# FPGA.net
KiCad netlist of a schematic drawn in Altium Designer
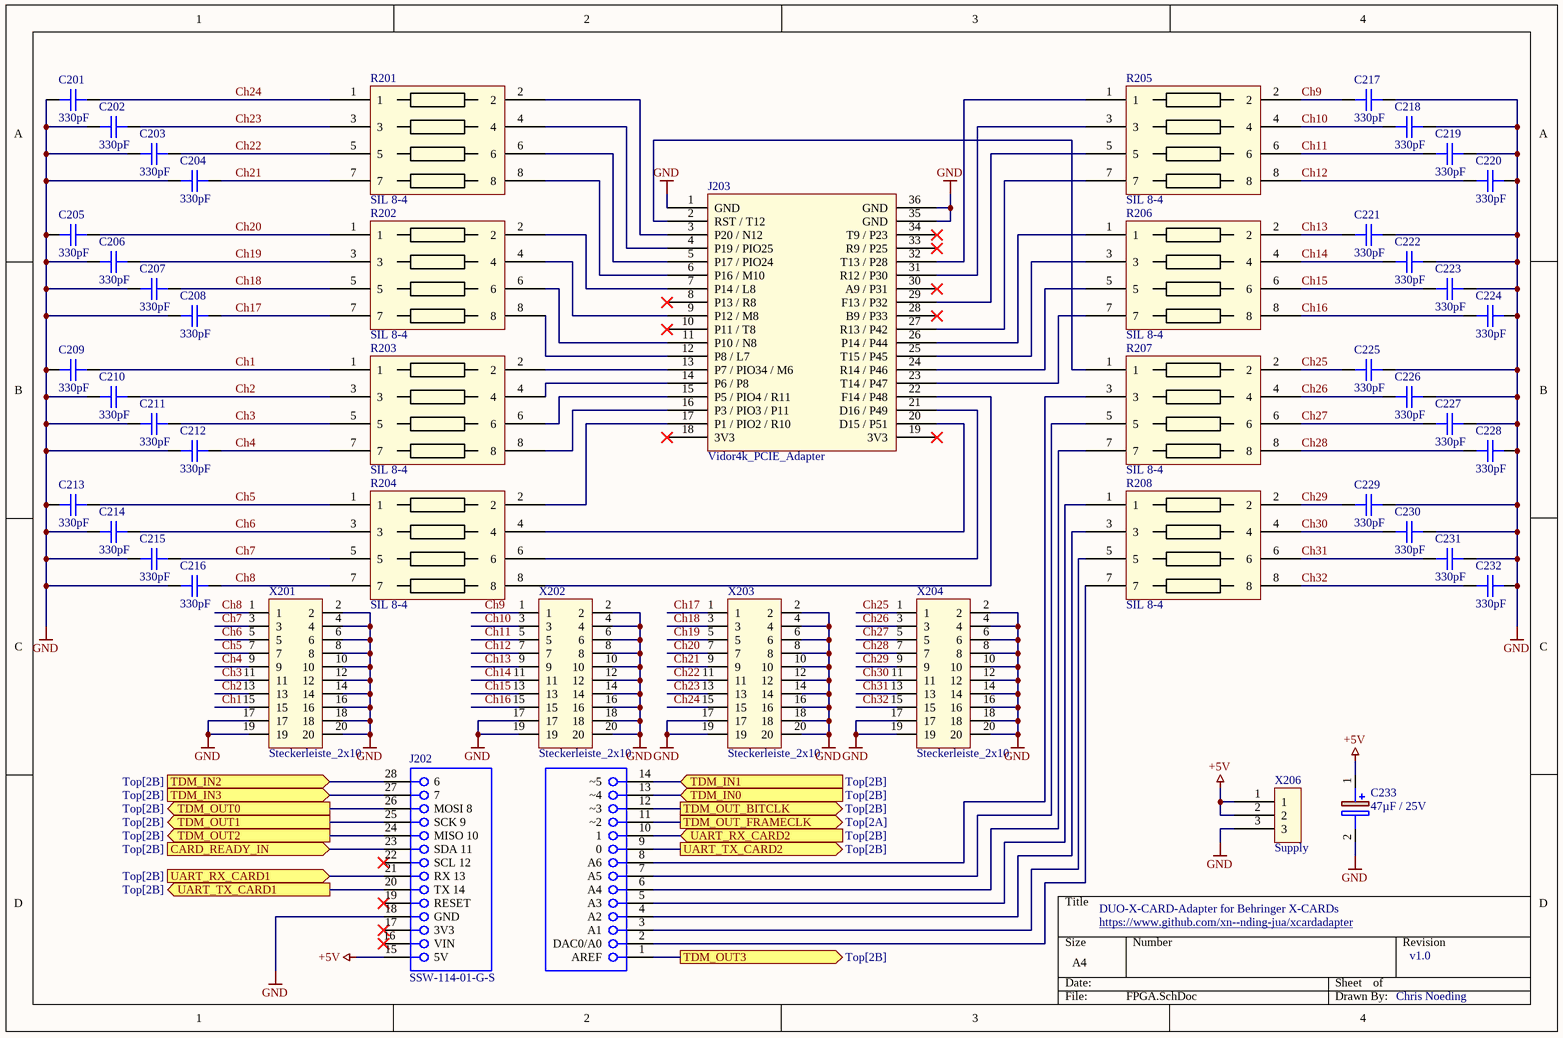
[diagram p0: FPGA.SchDoc]

(export (version "E")
  (design (tool "Eeschema 10.0.6"))
  (components
    (comp (ref "C201")
      (value "330pF")
      (footprint "1206")
      (description "1206_C")
      (libsource (lib "FPGA_Board_Library") (part "1206_C_1nF/63V"))
    )
    (comp (ref "C202")
      (value "330pF")
      (footprint "1206")
      (description "1206_C")
      (libsource (lib "FPGA_Board_Library") (part "1206_C_1nF/63V"))
    )
    (comp (ref "C203")
      (value "330pF")
      (footprint "1206")
      (description "1206_C")
      (libsource (lib "FPGA_Board_Library") (part "1206_C_1nF/63V"))
    )
    (comp (ref "C204")
      (value "330pF")
      (footprint "1206")
      (description "1206_C")
      (libsource (lib "FPGA_Board_Library") (part "1206_C_1nF/63V"))
    )
    (comp (ref "C205")
      (value "330pF")
      (footprint "1206")
      (description "1206_C")
      (libsource (lib "FPGA_Board_Library") (part "1206_C_1nF/63V"))
    )
    (comp (ref "C206")
      (value "330pF")
      (footprint "1206")
      (description "1206_C")
      (libsource (lib "FPGA_Board_Library") (part "1206_C_1nF/63V"))
    )
    (comp (ref "C207")
      (value "330pF")
      (footprint "1206")
      (description "1206_C")
      (libsource (lib "FPGA_Board_Library") (part "1206_C_1nF/63V"))
    )
    (comp (ref "C208")
      (value "330pF")
      (footprint "1206")
      (description "1206_C")
      (libsource (lib "FPGA_Board_Library") (part "1206_C_1nF/63V"))
    )
    (comp (ref "C209")
      (value "330pF")
      (footprint "1206")
      (description "1206_C")
      (libsource (lib "FPGA_Board_Library") (part "1206_C_1nF/63V"))
    )
    (comp (ref "C210")
      (value "330pF")
      (footprint "1206")
      (description "1206_C")
      (libsource (lib "FPGA_Board_Library") (part "1206_C_1nF/63V"))
    )
    (comp (ref "C211")
      (value "330pF")
      (footprint "1206")
      (description "1206_C")
      (libsource (lib "FPGA_Board_Library") (part "1206_C_1nF/63V"))
    )
    (comp (ref "C212")
      (value "330pF")
      (footprint "1206")
      (description "1206_C")
      (libsource (lib "FPGA_Board_Library") (part "1206_C_1nF/63V"))
    )
    (comp (ref "C213")
      (value "330pF")
      (footprint "1206")
      (description "1206_C")
      (libsource (lib "FPGA_Board_Library") (part "1206_C_1nF/63V"))
    )
    (comp (ref "C214")
      (value "330pF")
      (footprint "1206")
      (description "1206_C")
      (libsource (lib "FPGA_Board_Library") (part "1206_C_1nF/63V"))
    )
    (comp (ref "C215")
      (value "330pF")
      (footprint "1206")
      (description "1206_C")
      (libsource (lib "FPGA_Board_Library") (part "1206_C_1nF/63V"))
    )
    (comp (ref "C216")
      (value "330pF")
      (footprint "1206")
      (description "1206_C")
      (libsource (lib "FPGA_Board_Library") (part "1206_C_1nF/63V"))
    )
    (comp (ref "C217")
      (value "330pF")
      (footprint "1206")
      (description "1206_C")
      (libsource (lib "FPGA_Board_Library") (part "1206_C_1nF/63V"))
    )
    (comp (ref "C218")
      (value "330pF")
      (footprint "1206")
      (description "1206_C")
      (libsource (lib "FPGA_Board_Library") (part "1206_C_1nF/63V"))
    )
    (comp (ref "C219")
      (value "330pF")
      (footprint "1206")
      (description "1206_C")
      (libsource (lib "FPGA_Board_Library") (part "1206_C_1nF/63V"))
    )
    (comp (ref "C220")
      (value "330pF")
      (footprint "1206")
      (description "1206_C")
      (libsource (lib "FPGA_Board_Library") (part "1206_C_1nF/63V"))
    )
    (comp (ref "C221")
      (value "330pF")
      (footprint "1206")
      (description "1206_C")
      (libsource (lib "FPGA_Board_Library") (part "1206_C_1nF/63V"))
    )
    (comp (ref "C222")
      (value "330pF")
      (footprint "1206")
      (description "1206_C")
      (libsource (lib "FPGA_Board_Library") (part "1206_C_1nF/63V"))
    )
    (comp (ref "C223")
      (value "330pF")
      (footprint "1206")
      (description "1206_C")
      (libsource (lib "FPGA_Board_Library") (part "1206_C_1nF/63V"))
    )
    (comp (ref "C224")
      (value "330pF")
      (footprint "1206")
      (description "1206_C")
      (libsource (lib "FPGA_Board_Library") (part "1206_C_1nF/63V"))
    )
    (comp (ref "C225")
      (value "330pF")
      (footprint "1206")
      (description "1206_C")
      (libsource (lib "FPGA_Board_Library") (part "1206_C_1nF/63V"))
    )
    (comp (ref "C226")
      (value "330pF")
      (footprint "1206")
      (description "1206_C")
      (libsource (lib "FPGA_Board_Library") (part "1206_C_1nF/63V"))
    )
    (comp (ref "C227")
      (value "330pF")
      (footprint "1206")
      (description "1206_C")
      (libsource (lib "FPGA_Board_Library") (part "1206_C_1nF/63V"))
    )
    (comp (ref "C228")
      (value "330pF")
      (footprint "1206")
      (description "1206_C")
      (libsource (lib "FPGA_Board_Library") (part "1206_C_1nF/63V"))
    )
    (comp (ref "C229")
      (value "330pF")
      (footprint "1206")
      (description "1206_C")
      (libsource (lib "FPGA_Board_Library") (part "1206_C_1nF/63V"))
    )
    (comp (ref "C230")
      (value "330pF")
      (footprint "1206")
      (description "1206_C")
      (libsource (lib "FPGA_Board_Library") (part "1206_C_1nF/63V"))
    )
    (comp (ref "C231")
      (value "330pF")
      (footprint "1206")
      (description "1206_C")
      (libsource (lib "FPGA_Board_Library") (part "1206_C_1nF/63V"))
    )
    (comp (ref "C232")
      (value "330pF")
      (footprint "1206")
      (description "1206_C")
      (libsource (lib "FPGA_Board_Library") (part "1206_C_1nF/63V"))
    )
    (comp (ref "C233")
      (value "47µF / 25V")
      (footprint "SamacSys:CAPPRD200W50D550H1250")
      (description "Capacitor Polarised")
      (fields (field (name "MANUFACTURER_PART_NUMBER") "MAL214256479E3"))
      (libsource (lib "*") (part "MAL214256479E3"))
    )
    (comp (ref "J202")
      (value "SSW-114-01-G-S")
      (footprint "SMTC-SSW-114-01-X-S")
      (description "SQ Post Socket, Through-hole, Vertical, -55 to 125 degC, 2.54 mm Pitch, 14-Pin, Female, RoHS")
      (fields (field (name "MANUFACTURER") "Samtec"))
      (libsource (lib "SamacSys") (part "Arduino MKR Vidor 4000"))
    )
    (comp (ref "J203")
      (value "Vidor4k_PCIE_Adapter")
      (footprint "Vidor4K_PCIE_Adapter")
      (libsource (lib "SamacSys") (part "Vidor4k_PCIE_Adapter"))
    )
    (comp (ref "R201")
      (value "SIL 8-4")
      (footprint "SIL8")
      (libsource (lib "XCARD_Adapter") (part "SIL 8-4"))
    )
    (comp (ref "R202")
      (value "SIL 8-4")
      (footprint "SIL8")
      (libsource (lib "XCARD_Adapter") (part "SIL 8-4"))
    )
    (comp (ref "R203")
      (value "SIL 8-4")
      (footprint "SIL8")
      (libsource (lib "XCARD_Adapter") (part "SIL 8-4"))
    )
    (comp (ref "R204")
      (value "SIL 8-4")
      (footprint "SIL8")
      (libsource (lib "XCARD_Adapter") (part "SIL 8-4"))
    )
    (comp (ref "R205")
      (value "SIL 8-4")
      (footprint "SIL8")
      (libsource (lib "XCARD_Adapter") (part "SIL 8-4"))
    )
    (comp (ref "R206")
      (value "SIL 8-4")
      (footprint "SIL8")
      (libsource (lib "XCARD_Adapter") (part "SIL 8-4"))
    )
    (comp (ref "R207")
      (value "SIL 8-4")
      (footprint "SIL8")
      (libsource (lib "XCARD_Adapter") (part "SIL 8-4"))
    )
    (comp (ref "R208")
      (value "SIL 8-4")
      (footprint "SIL8")
      (libsource (lib "XCARD_Adapter") (part "SIL 8-4"))
    )
    (comp (ref "X201")
      (value "Steckerleiste_2x10")
      (footprint "steckerleiste_2x10")
      (libsource (lib "FPGA_Board_Library") (part "Steckerleiste_2x10"))
    )
    (comp (ref "X202")
      (value "Steckerleiste_2x10")
      (footprint "steckerleiste_2x10")
      (libsource (lib "FPGA_Board_Library") (part "Steckerleiste_2x10"))
    )
    (comp (ref "X203")
      (value "Steckerleiste_2x10")
      (footprint "steckerleiste_2x10")
      (libsource (lib "FPGA_Board_Library") (part "Steckerleiste_2x10"))
    )
    (comp (ref "X204")
      (value "Steckerleiste_2x10")
      (footprint "steckerleiste_2x10")
      (libsource (lib "FPGA_Board_Library") (part "Steckerleiste_2x10"))
    )
    (comp (ref "X206")
      (value "Supply")
      (footprint "1x3 Jumper")
      (libsource (lib "KDEE_HiResPG") (part "1x3 Jumper"))
    )
  )
  (nets
    (net (code "1") (name "+5V") (class "Default")
      (node (ref "C233") (pin "1") (pinfunction "+_1") (pintype "passive"))
      (node (ref "J202") (pin "15") (pinfunction "5V_15") (pintype "passive"))
      (node (ref "X206") (pin "1") (pinfunction "1_1") (pintype "passive"))
      (node (ref "X206") (pin "2") (pinfunction "2_2") (pintype "passive"))
    )
    (net (code "2") (name "/CARD_READY_IN") (class "Default")
      (node (ref "J202") (pin "23") (pinfunction "SDA_11_23") (pintype "passive"))
    )
    (net (code "3") (name "/Ch1") (class "Default")
      (node (ref "C209") (pin "1") (pinfunction "1_1") (pintype "passive"))
      (node (ref "R203") (pin "1") (pinfunction "1_1") (pintype "passive"))
      (node (ref "X201") (pin "15") (pinfunction "15_15") (pintype "passive"))
    )
    (net (code "4") (name "/Ch2") (class "Default")
      (node (ref "C210") (pin "1") (pinfunction "1_1") (pintype "passive"))
      (node (ref "R203") (pin "3") (pinfunction "3_3") (pintype "passive"))
      (node (ref "X201") (pin "13") (pinfunction "13_13") (pintype "passive"))
    )
    (net (code "5") (name "/Ch3") (class "Default")
      (node (ref "C211") (pin "1") (pinfunction "1_1") (pintype "passive"))
      (node (ref "R203") (pin "5") (pinfunction "5_5") (pintype "passive"))
      (node (ref "X201") (pin "11") (pinfunction "11_11") (pintype "passive"))
    )
    (net (code "6") (name "/Ch4") (class "Default")
      (node (ref "C212") (pin "1") (pinfunction "1_1") (pintype "passive"))
      (node (ref "R203") (pin "7") (pinfunction "7_7") (pintype "passive"))
      (node (ref "X201") (pin "9") (pinfunction "9_9") (pintype "passive"))
    )
    (net (code "7") (name "/Ch5") (class "Default")
      (node (ref "C213") (pin "1") (pinfunction "1_1") (pintype "passive"))
      (node (ref "R204") (pin "1") (pinfunction "1_1") (pintype "passive"))
      (node (ref "X201") (pin "7") (pinfunction "7_7") (pintype "passive"))
    )
    (net (code "8") (name "/Ch6") (class "Default")
      (node (ref "C214") (pin "1") (pinfunction "1_1") (pintype "passive"))
      (node (ref "R204") (pin "3") (pinfunction "3_3") (pintype "passive"))
      (node (ref "X201") (pin "5") (pinfunction "5_5") (pintype "passive"))
    )
    (net (code "9") (name "/Ch7") (class "Default")
      (node (ref "C215") (pin "1") (pinfunction "1_1") (pintype "passive"))
      (node (ref "R204") (pin "5") (pinfunction "5_5") (pintype "passive"))
      (node (ref "X201") (pin "3") (pinfunction "3_3") (pintype "passive"))
    )
    (net (code "10") (name "/Ch8") (class "Default")
      (node (ref "C216") (pin "1") (pinfunction "1_1") (pintype "passive"))
      (node (ref "R204") (pin "7") (pinfunction "7_7") (pintype "passive"))
      (node (ref "X201") (pin "1") (pinfunction "1_1") (pintype "passive"))
    )
    (net (code "11") (name "/Ch9") (class "Default")
      (node (ref "C217") (pin "2") (pinfunction "2_2") (pintype "passive"))
      (node (ref "R205") (pin "2") (pinfunction "2_2") (pintype "passive"))
      (node (ref "X202") (pin "1") (pinfunction "1_1") (pintype "passive"))
    )
    (net (code "12") (name "/Ch10") (class "Default")
      (node (ref "C218") (pin "2") (pinfunction "2_2") (pintype "passive"))
      (node (ref "R205") (pin "4") (pinfunction "4_4") (pintype "passive"))
      (node (ref "X202") (pin "3") (pinfunction "3_3") (pintype "passive"))
    )
    (net (code "13") (name "/Ch11") (class "Default")
      (node (ref "C219") (pin "2") (pinfunction "2_2") (pintype "passive"))
      (node (ref "R205") (pin "6") (pinfunction "6_6") (pintype "passive"))
      (node (ref "X202") (pin "5") (pinfunction "5_5") (pintype "passive"))
    )
    (net (code "14") (name "/Ch12") (class "Default")
      (node (ref "C220") (pin "2") (pinfunction "2_2") (pintype "passive"))
      (node (ref "R205") (pin "8") (pinfunction "8_8") (pintype "passive"))
      (node (ref "X202") (pin "7") (pinfunction "7_7") (pintype "passive"))
    )
    (net (code "15") (name "/Ch13") (class "Default")
      (node (ref "C221") (pin "2") (pinfunction "2_2") (pintype "passive"))
      (node (ref "R206") (pin "2") (pinfunction "2_2") (pintype "passive"))
      (node (ref "X202") (pin "9") (pinfunction "9_9") (pintype "passive"))
    )
    (net (code "16") (name "/Ch14") (class "Default")
      (node (ref "C222") (pin "2") (pinfunction "2_2") (pintype "passive"))
      (node (ref "R206") (pin "4") (pinfunction "4_4") (pintype "passive"))
      (node (ref "X202") (pin "11") (pinfunction "11_11") (pintype "passive"))
    )
    (net (code "17") (name "/Ch15") (class "Default")
      (node (ref "C223") (pin "2") (pinfunction "2_2") (pintype "passive"))
      (node (ref "R206") (pin "6") (pinfunction "6_6") (pintype "passive"))
      (node (ref "X202") (pin "13") (pinfunction "13_13") (pintype "passive"))
    )
    (net (code "18") (name "/Ch16") (class "Default")
      (node (ref "C224") (pin "2") (pinfunction "2_2") (pintype "passive"))
      (node (ref "R206") (pin "8") (pinfunction "8_8") (pintype "passive"))
      (node (ref "X202") (pin "15") (pinfunction "15_15") (pintype "passive"))
    )
    (net (code "19") (name "/Ch17") (class "Default")
      (node (ref "C208") (pin "1") (pinfunction "1_1") (pintype "passive"))
      (node (ref "R202") (pin "7") (pinfunction "7_7") (pintype "passive"))
      (node (ref "X203") (pin "1") (pinfunction "1_1") (pintype "passive"))
    )
    (net (code "20") (name "/Ch18") (class "Default")
      (node (ref "C207") (pin "1") (pinfunction "1_1") (pintype "passive"))
      (node (ref "R202") (pin "5") (pinfunction "5_5") (pintype "passive"))
      (node (ref "X203") (pin "3") (pinfunction "3_3") (pintype "passive"))
    )
    (net (code "21") (name "/Ch19") (class "Default")
      (node (ref "C206") (pin "1") (pinfunction "1_1") (pintype "passive"))
      (node (ref "R202") (pin "3") (pinfunction "3_3") (pintype "passive"))
      (node (ref "X203") (pin "5") (pinfunction "5_5") (pintype "passive"))
    )
    (net (code "22") (name "/Ch20") (class "Default")
      (node (ref "C205") (pin "1") (pinfunction "1_1") (pintype "passive"))
      (node (ref "R202") (pin "1") (pinfunction "1_1") (pintype "passive"))
      (node (ref "X203") (pin "7") (pinfunction "7_7") (pintype "passive"))
    )
    (net (code "23") (name "/Ch21") (class "Default")
      (node (ref "C204") (pin "1") (pinfunction "1_1") (pintype "passive"))
      (node (ref "R201") (pin "7") (pinfunction "7_7") (pintype "passive"))
      (node (ref "X203") (pin "9") (pinfunction "9_9") (pintype "passive"))
    )
    (net (code "24") (name "/Ch22") (class "Default")
      (node (ref "C203") (pin "1") (pinfunction "1_1") (pintype "passive"))
      (node (ref "R201") (pin "5") (pinfunction "5_5") (pintype "passive"))
      (node (ref "X203") (pin "11") (pinfunction "11_11") (pintype "passive"))
    )
    (net (code "25") (name "/Ch23") (class "Default")
      (node (ref "C202") (pin "1") (pinfunction "1_1") (pintype "passive"))
      (node (ref "R201") (pin "3") (pinfunction "3_3") (pintype "passive"))
      (node (ref "X203") (pin "13") (pinfunction "13_13") (pintype "passive"))
    )
    (net (code "26") (name "/Ch24") (class "Default")
      (node (ref "C201") (pin "1") (pinfunction "1_1") (pintype "passive"))
      (node (ref "R201") (pin "1") (pinfunction "1_1") (pintype "passive"))
      (node (ref "X203") (pin "15") (pinfunction "15_15") (pintype "passive"))
    )
    (net (code "27") (name "/Ch25") (class "Default")
      (node (ref "C225") (pin "2") (pinfunction "2_2") (pintype "passive"))
      (node (ref "R207") (pin "2") (pinfunction "2_2") (pintype "passive"))
      (node (ref "X204") (pin "1") (pinfunction "1_1") (pintype "passive"))
    )
    (net (code "28") (name "/Ch26") (class "Default")
      (node (ref "C226") (pin "2") (pinfunction "2_2") (pintype "passive"))
      (node (ref "R207") (pin "4") (pinfunction "4_4") (pintype "passive"))
      (node (ref "X204") (pin "3") (pinfunction "3_3") (pintype "passive"))
    )
    (net (code "29") (name "/Ch27") (class "Default")
      (node (ref "C227") (pin "2") (pinfunction "2_2") (pintype "passive"))
      (node (ref "R207") (pin "6") (pinfunction "6_6") (pintype "passive"))
      (node (ref "X204") (pin "5") (pinfunction "5_5") (pintype "passive"))
    )
    (net (code "30") (name "/Ch28") (class "Default")
      (node (ref "C228") (pin "2") (pinfunction "2_2") (pintype "passive"))
      (node (ref "R207") (pin "8") (pinfunction "8_8") (pintype "passive"))
      (node (ref "X204") (pin "7") (pinfunction "7_7") (pintype "passive"))
    )
    (net (code "31") (name "/Ch29") (class "Default")
      (node (ref "C229") (pin "2") (pinfunction "2_2") (pintype "passive"))
      (node (ref "R208") (pin "2") (pinfunction "2_2") (pintype "passive"))
      (node (ref "X204") (pin "9") (pinfunction "9_9") (pintype "passive"))
    )
    (net (code "32") (name "/Ch30") (class "Default")
      (node (ref "C230") (pin "2") (pinfunction "2_2") (pintype "passive"))
      (node (ref "R208") (pin "4") (pinfunction "4_4") (pintype "passive"))
      (node (ref "X204") (pin "11") (pinfunction "11_11") (pintype "passive"))
    )
    (net (code "33") (name "/Ch31") (class "Default")
      (node (ref "C231") (pin "2") (pinfunction "2_2") (pintype "passive"))
      (node (ref "R208") (pin "6") (pinfunction "6_6") (pintype "passive"))
      (node (ref "X204") (pin "13") (pinfunction "13_13") (pintype "passive"))
    )
    (net (code "34") (name "/Ch32") (class "Default")
      (node (ref "C232") (pin "2") (pinfunction "2_2") (pintype "passive"))
      (node (ref "R208") (pin "8") (pinfunction "8_8") (pintype "passive"))
      (node (ref "X204") (pin "15") (pinfunction "15_15") (pintype "passive"))
    )
    (net (code "35") (name "/TDM_IN0") (class "Default")
      (node (ref "J202") (pin "13") (pinfunction "~4_13") (pintype "passive"))
    )
    (net (code "36") (name "/TDM_IN1") (class "Default")
      (node (ref "J202") (pin "14") (pinfunction "~5_14") (pintype "passive"))
    )
    (net (code "37") (name "/TDM_IN2") (class "Default")
      (node (ref "J202") (pin "28") (pinfunction "6_28") (pintype "passive"))
    )
    (net (code "38") (name "/TDM_IN3") (class "Default")
      (node (ref "J202") (pin "27") (pinfunction "7_27") (pintype "passive"))
    )
    (net (code "39") (name "/TDM_OUT0") (class "Default")
      (node (ref "J202") (pin "26") (pinfunction "MOSI_8_26") (pintype "passive"))
    )
    (net (code "40") (name "/TDM_OUT1") (class "Default")
      (node (ref "J202") (pin "25") (pinfunction "SCK_9_25") (pintype "passive"))
    )
    (net (code "41") (name "/TDM_OUT2") (class "Default")
      (node (ref "J202") (pin "24") (pinfunction "MISO_10_24") (pintype "passive"))
    )
    (net (code "42") (name "/TDM_OUT3") (class "Default")
      (node (ref "J202") (pin "1") (pinfunction "AREF_1") (pintype "passive"))
    )
    (net (code "43") (name "/TDM_OUT_BITCLK") (class "Default")
      (node (ref "J202") (pin "12") (pinfunction "~3_12") (pintype "passive"))
    )
    (net (code "44") (name "/TDM_OUT_FRAMECLK") (class "Default")
      (node (ref "J202") (pin "11") (pinfunction "~2_11") (pintype "passive"))
    )
    (net (code "45") (name "/UART_RX_CARD1") (class "Default")
      (node (ref "J202") (pin "21") (pinfunction "RX_13_21") (pintype "passive"))
    )
    (net (code "46") (name "/UART_RX_CARD2") (class "Default")
      (node (ref "J202") (pin "10") (pinfunction "1_10") (pintype "passive"))
    )
    (net (code "47") (name "/UART_TX_CARD1") (class "Default")
      (node (ref "J202") (pin "20") (pinfunction "TX_14_20") (pintype "passive"))
    )
    (net (code "48") (name "/UART_TX_CARD2") (class "Default")
      (node (ref "J202") (pin "9") (pinfunction "0_9") (pintype "passive"))
    )
    (net (code "49") (name "GND") (class "Default")
      (node (ref "C201") (pin "2") (pinfunction "2_2") (pintype "passive"))
      (node (ref "C202") (pin "2") (pinfunction "2_2") (pintype "passive"))
      (node (ref "C203") (pin "2") (pinfunction "2_2") (pintype "passive"))
      (node (ref "C204") (pin "2") (pinfunction "2_2") (pintype "passive"))
      (node (ref "C205") (pin "2") (pinfunction "2_2") (pintype "passive"))
      (node (ref "C206") (pin "2") (pinfunction "2_2") (pintype "passive"))
      (node (ref "C207") (pin "2") (pinfunction "2_2") (pintype "passive"))
      (node (ref "C208") (pin "2") (pinfunction "2_2") (pintype "passive"))
      (node (ref "C209") (pin "2") (pinfunction "2_2") (pintype "passive"))
      (node (ref "C210") (pin "2") (pinfunction "2_2") (pintype "passive"))
      (node (ref "C211") (pin "2") (pinfunction "2_2") (pintype "passive"))
      (node (ref "C212") (pin "2") (pinfunction "2_2") (pintype "passive"))
      (node (ref "C213") (pin "2") (pinfunction "2_2") (pintype "passive"))
      (node (ref "C214") (pin "2") (pinfunction "2_2") (pintype "passive"))
      (node (ref "C215") (pin "2") (pinfunction "2_2") (pintype "passive"))
      (node (ref "C216") (pin "2") (pinfunction "2_2") (pintype "passive"))
      (node (ref "C217") (pin "1") (pinfunction "1_1") (pintype "passive"))
      (node (ref "C218") (pin "1") (pinfunction "1_1") (pintype "passive"))
      (node (ref "C219") (pin "1") (pinfunction "1_1") (pintype "passive"))
      (node (ref "C220") (pin "1") (pinfunction "1_1") (pintype "passive"))
      (node (ref "C221") (pin "1") (pinfunction "1_1") (pintype "passive"))
      (node (ref "C222") (pin "1") (pinfunction "1_1") (pintype "passive"))
      (node (ref "C223") (pin "1") (pinfunction "1_1") (pintype "passive"))
      (node (ref "C224") (pin "1") (pinfunction "1_1") (pintype "passive"))
      (node (ref "C225") (pin "1") (pinfunction "1_1") (pintype "passive"))
      (node (ref "C226") (pin "1") (pinfunction "1_1") (pintype "passive"))
      (node (ref "C227") (pin "1") (pinfunction "1_1") (pintype "passive"))
      (node (ref "C228") (pin "1") (pinfunction "1_1") (pintype "passive"))
      (node (ref "C229") (pin "1") (pinfunction "1_1") (pintype "passive"))
      (node (ref "C230") (pin "1") (pinfunction "1_1") (pintype "passive"))
      (node (ref "C231") (pin "1") (pinfunction "1_1") (pintype "passive"))
      (node (ref "C232") (pin "1") (pinfunction "1_1") (pintype "passive"))
      (node (ref "C233") (pin "2") (pinfunction "-_2") (pintype "passive"))
      (node (ref "J202") (pin "18") (pinfunction "GND_18") (pintype "passive"))
      (node (ref "J203") (pin "1") (pinfunction "GND_1") (pintype "passive"))
      (node (ref "J203") (pin "35") (pinfunction "GND_35") (pintype "passive"))
      (node (ref "J203") (pin "36") (pinfunction "GND_36") (pintype "passive"))
      (node (ref "X201") (pin "10") (pinfunction "10_10") (pintype "passive"))
      (node (ref "X201") (pin "12") (pinfunction "12_12") (pintype "passive"))
      (node (ref "X201") (pin "14") (pinfunction "14_14") (pintype "passive"))
      (node (ref "X201") (pin "16") (pinfunction "16_16") (pintype "passive"))
      (node (ref "X201") (pin "17") (pinfunction "17_17") (pintype "passive"))
      (node (ref "X201") (pin "18") (pinfunction "18_18") (pintype "passive"))
      (node (ref "X201") (pin "19") (pinfunction "19_19") (pintype "passive"))
      (node (ref "X201") (pin "2") (pinfunction "2_2") (pintype "passive"))
      (node (ref "X201") (pin "20") (pinfunction "20_20") (pintype "passive"))
      (node (ref "X201") (pin "4") (pinfunction "4_4") (pintype "passive"))
      (node (ref "X201") (pin "6") (pinfunction "6_6") (pintype "passive"))
      (node (ref "X201") (pin "8") (pinfunction "8_8") (pintype "passive"))
      (node (ref "X202") (pin "10") (pinfunction "10_10") (pintype "passive"))
      (node (ref "X202") (pin "12") (pinfunction "12_12") (pintype "passive"))
      (node (ref "X202") (pin "14") (pinfunction "14_14") (pintype "passive"))
      (node (ref "X202") (pin "16") (pinfunction "16_16") (pintype "passive"))
      (node (ref "X202") (pin "17") (pinfunction "17_17") (pintype "passive"))
      (node (ref "X202") (pin "18") (pinfunction "18_18") (pintype "passive"))
      (node (ref "X202") (pin "19") (pinfunction "19_19") (pintype "passive"))
      (node (ref "X202") (pin "2") (pinfunction "2_2") (pintype "passive"))
      (node (ref "X202") (pin "20") (pinfunction "20_20") (pintype "passive"))
      (node (ref "X202") (pin "4") (pinfunction "4_4") (pintype "passive"))
      (node (ref "X202") (pin "6") (pinfunction "6_6") (pintype "passive"))
      (node (ref "X202") (pin "8") (pinfunction "8_8") (pintype "passive"))
      (node (ref "X203") (pin "10") (pinfunction "10_10") (pintype "passive"))
      (node (ref "X203") (pin "12") (pinfunction "12_12") (pintype "passive"))
      (node (ref "X203") (pin "14") (pinfunction "14_14") (pintype "passive"))
      (node (ref "X203") (pin "16") (pinfunction "16_16") (pintype "passive"))
      (node (ref "X203") (pin "17") (pinfunction "17_17") (pintype "passive"))
      (node (ref "X203") (pin "18") (pinfunction "18_18") (pintype "passive"))
      (node (ref "X203") (pin "19") (pinfunction "19_19") (pintype "passive"))
      (node (ref "X203") (pin "2") (pinfunction "2_2") (pintype "passive"))
      (node (ref "X203") (pin "20") (pinfunction "20_20") (pintype "passive"))
      (node (ref "X203") (pin "4") (pinfunction "4_4") (pintype "passive"))
      (node (ref "X203") (pin "6") (pinfunction "6_6") (pintype "passive"))
      (node (ref "X203") (pin "8") (pinfunction "8_8") (pintype "passive"))
      (node (ref "X204") (pin "10") (pinfunction "10_10") (pintype "passive"))
      (node (ref "X204") (pin "12") (pinfunction "12_12") (pintype "passive"))
      (node (ref "X204") (pin "14") (pinfunction "14_14") (pintype "passive"))
      (node (ref "X204") (pin "16") (pinfunction "16_16") (pintype "passive"))
      (node (ref "X204") (pin "17") (pinfunction "17_17") (pintype "passive"))
      (node (ref "X204") (pin "18") (pinfunction "18_18") (pintype "passive"))
      (node (ref "X204") (pin "19") (pinfunction "19_19") (pintype "passive"))
      (node (ref "X204") (pin "2") (pinfunction "2_2") (pintype "passive"))
      (node (ref "X204") (pin "20") (pinfunction "20_20") (pintype "passive"))
      (node (ref "X204") (pin "4") (pinfunction "4_4") (pintype "passive"))
      (node (ref "X204") (pin "6") (pinfunction "6_6") (pintype "passive"))
      (node (ref "X204") (pin "8") (pinfunction "8_8") (pintype "passive"))
      (node (ref "X206") (pin "3") (pinfunction "3_3") (pintype "passive"))
    )
    (net (code "50") (name "Net-(J202-A1)") (class "Default")
      (node (ref "J202") (pin "3") (pinfunction "A1_3") (pintype "passive"))
      (node (ref "R208") (pin "5") (pinfunction "5_5") (pintype "passive"))
    )
    (net (code "51") (name "Net-(J202-A2)") (class "Default")
      (node (ref "J202") (pin "4") (pinfunction "A2_4") (pintype "passive"))
      (node (ref "R208") (pin "3") (pinfunction "3_3") (pintype "passive"))
    )
    (net (code "52") (name "Net-(J202-A3)") (class "Default")
      (node (ref "J202") (pin "5") (pinfunction "A3_5") (pintype "passive"))
      (node (ref "R208") (pin "1") (pinfunction "1_1") (pintype "passive"))
    )
    (net (code "53") (name "Net-(J202-A4)") (class "Default")
      (node (ref "J202") (pin "6") (pinfunction "A4_6") (pintype "passive"))
      (node (ref "R207") (pin "7") (pinfunction "7_7") (pintype "passive"))
    )
    (net (code "54") (name "Net-(J202-A5)") (class "Default")
      (node (ref "J202") (pin "7") (pinfunction "A5_7") (pintype "passive"))
      (node (ref "R207") (pin "5") (pinfunction "5_5") (pintype "passive"))
    )
    (net (code "55") (name "Net-(J202-A6)") (class "Default")
      (node (ref "J202") (pin "8") (pinfunction "A6_8") (pintype "passive"))
      (node (ref "R207") (pin "3") (pinfunction "3_3") (pintype "passive"))
    )
    (net (code "56") (name "Net-(J202-DAC0{slash}A0)") (class "Default")
      (node (ref "J202") (pin "2") (pinfunction "DAC0/A0_2") (pintype "passive"))
      (node (ref "R208") (pin "7") (pinfunction "7_7") (pintype "passive"))
    )
    (net (code "57") (name "Net-(J203-D15_{slash}_P51)") (class "Default")
      (node (ref "J203") (pin "20") (pinfunction "D15_/_P51_20") (pintype "passive"))
      (node (ref "R204") (pin "4") (pinfunction "4_4") (pintype "passive"))
    )
    (net (code "58") (name "Net-(J203-D16_{slash}_P49)") (class "Default")
      (node (ref "J203") (pin "21") (pinfunction "D16_/_P49_21") (pintype "passive"))
      (node (ref "R204") (pin "6") (pinfunction "6_6") (pintype "passive"))
    )
    (net (code "59") (name "Net-(J203-F13_{slash}_P32)") (class "Default")
      (node (ref "J203") (pin "29") (pinfunction "F13_/_P32_29") (pintype "passive"))
      (node (ref "R205") (pin "5") (pinfunction "5_5") (pintype "passive"))
    )
    (net (code "60") (name "Net-(J203-F14_{slash}_P48)") (class "Default")
      (node (ref "J203") (pin "22") (pinfunction "F14_/_P48_22") (pintype "passive"))
      (node (ref "R204") (pin "8") (pinfunction "8_8") (pintype "passive"))
    )
    (net (code "61") (name "Net-(J203-P1_{slash}_PIO2_{slash}_R10)") (class "Default")
      (node (ref "J203") (pin "17") (pinfunction "P1_/_PIO2_/_R10_17") (pintype "passive"))
      (node (ref "R204") (pin "2") (pinfunction "2_2") (pintype "passive"))
    )
    (net (code "62") (name "Net-(J203-P3_{slash}_PIO3_{slash}_P11)") (class "Default")
      (node (ref "J203") (pin "16") (pinfunction "P3_/_PIO3_/_P11_16") (pintype "passive"))
      (node (ref "R203") (pin "8") (pinfunction "8_8") (pintype "passive"))
    )
    (net (code "63") (name "Net-(J203-P5_{slash}_PIO4_{slash}_R11)") (class "Default")
      (node (ref "J203") (pin "15") (pinfunction "P5_/_PIO4_/_R11_15") (pintype "passive"))
      (node (ref "R203") (pin "6") (pinfunction "6_6") (pintype "passive"))
    )
    (net (code "64") (name "Net-(J203-P6_{slash}_P8)") (class "Default")
      (node (ref "J203") (pin "14") (pinfunction "P6_/_P8_14") (pintype "passive"))
      (node (ref "R203") (pin "4") (pinfunction "4_4") (pintype "passive"))
    )
    (net (code "65") (name "Net-(J203-P7_{slash}_PIO34_{slash}_M6)") (class "Default")
      (node (ref "J203") (pin "13") (pinfunction "P7_/_PIO34_/_M6_13") (pintype "passive"))
      (node (ref "R203") (pin "2") (pinfunction "2_2") (pintype "passive"))
    )
    (net (code "66") (name "Net-(J203-P8_{slash}_L7)") (class "Default")
      (node (ref "J203") (pin "12") (pinfunction "P8_/_L7_12") (pintype "passive"))
      (node (ref "R202") (pin "8") (pinfunction "8_8") (pintype "passive"))
    )
    (net (code "67") (name "Net-(J203-P10_{slash}_N8)") (class "Default")
      (node (ref "J203") (pin "11") (pinfunction "P10_/_N8_11") (pintype "passive"))
      (node (ref "R202") (pin "6") (pinfunction "6_6") (pintype "passive"))
    )
    (net (code "68") (name "Net-(J203-P12_{slash}_M8)") (class "Default")
      (node (ref "J203") (pin "9") (pinfunction "P12_/_M8_9") (pintype "passive"))
      (node (ref "R202") (pin "4") (pinfunction "4_4") (pintype "passive"))
    )
    (net (code "69") (name "Net-(J203-P14_{slash}_L8)") (class "Default")
      (node (ref "J203") (pin "7") (pinfunction "P14_/_L8_7") (pintype "passive"))
      (node (ref "R202") (pin "2") (pinfunction "2_2") (pintype "passive"))
    )
    (net (code "70") (name "Net-(J203-P14_{slash}_P44)") (class "Default")
      (node (ref "J203") (pin "26") (pinfunction "P14_/_P44_26") (pintype "passive"))
      (node (ref "R206") (pin "1") (pinfunction "1_1") (pintype "passive"))
    )
    (net (code "71") (name "Net-(J203-P16_{slash}_M10)") (class "Default")
      (node (ref "J203") (pin "6") (pinfunction "P16_/_M10_6") (pintype "passive"))
      (node (ref "R201") (pin "8") (pinfunction "8_8") (pintype "passive"))
    )
    (net (code "72") (name "Net-(J203-P17_{slash}_PIO24)") (class "Default")
      (node (ref "J203") (pin "5") (pinfunction "P17_/_PIO24_5") (pintype "passive"))
      (node (ref "R201") (pin "6") (pinfunction "6_6") (pintype "passive"))
    )
    (net (code "73") (name "Net-(J203-P19_{slash}_PIO25)") (class "Default")
      (node (ref "J203") (pin "4") (pinfunction "P19_/_PIO25_4") (pintype "passive"))
      (node (ref "R201") (pin "4") (pinfunction "4_4") (pintype "passive"))
    )
    (net (code "74") (name "Net-(J203-P20_{slash}_N12)") (class "Default")
      (node (ref "J203") (pin "3") (pinfunction "P20_/_N12_3") (pintype "passive"))
      (node (ref "R201") (pin "2") (pinfunction "2_2") (pintype "passive"))
    )
    (net (code "75") (name "Net-(J203-R12_{slash}_P30)") (class "Default")
      (node (ref "J203") (pin "31") (pinfunction "R12_/_P30_31") (pintype "passive"))
      (node (ref "R205") (pin "3") (pinfunction "3_3") (pintype "passive"))
    )
    (net (code "76") (name "Net-(J203-R13_{slash}_P42)") (class "Default")
      (node (ref "J203") (pin "27") (pinfunction "R13_/_P42_27") (pintype "passive"))
      (node (ref "R205") (pin "7") (pinfunction "7_7") (pintype "passive"))
    )
    (net (code "77") (name "Net-(J203-R14_{slash}_P46)") (class "Default")
      (node (ref "J203") (pin "24") (pinfunction "R14_/_P46_24") (pintype "passive"))
      (node (ref "R206") (pin "5") (pinfunction "5_5") (pintype "passive"))
    )
    (net (code "78") (name "Net-(J203-RST_{slash}_T12)") (class "Default")
      (node (ref "J203") (pin "2") (pinfunction "RST_/_T12_2") (pintype "passive"))
      (node (ref "R207") (pin "1") (pinfunction "1_1") (pintype "passive"))
    )
    (net (code "79") (name "Net-(J203-T13_{slash}_P28)") (class "Default")
      (node (ref "J203") (pin "32") (pinfunction "T13_/_P28_32") (pintype "passive"))
      (node (ref "R205") (pin "1") (pinfunction "1_1") (pintype "passive"))
    )
    (net (code "80") (name "Net-(J203-T14_{slash}_P47)") (class "Default")
      (node (ref "J203") (pin "23") (pinfunction "T14_/_P47_23") (pintype "passive"))
      (node (ref "R206") (pin "7") (pinfunction "7_7") (pintype "passive"))
    )
    (net (code "81") (name "Net-(J203-T15_{slash}_P45)") (class "Default")
      (node (ref "J203") (pin "25") (pinfunction "T15_/_P45_25") (pintype "passive"))
      (node (ref "R206") (pin "3") (pinfunction "3_3") (pintype "passive"))
    )
    (net (code "82") (name "unconnected-(J202-3V3-Pad17)") (class "Default")
      (node (ref "J202") (pin "17") (pinfunction "3V3_17") (pintype "passive+no_connect"))
    )
    (net (code "83") (name "unconnected-(J202-RESET-Pad19)") (class "Default")
      (node (ref "J202") (pin "19") (pinfunction "RESET_19") (pintype "passive+no_connect"))
    )
    (net (code "84") (name "unconnected-(J202-SCL_12-Pad22)") (class "Default")
      (node (ref "J202") (pin "22") (pinfunction "SCL_12_22") (pintype "passive+no_connect"))
    )
    (net (code "85") (name "unconnected-(J202-VIN-Pad16)") (class "Default")
      (node (ref "J202") (pin "16") (pinfunction "VIN_16") (pintype "passive+no_connect"))
    )
    (net (code "86") (name "unconnected-(J203-3V3-Pad18)") (class "Default")
      (node (ref "J203") (pin "18") (pinfunction "3V3_18") (pintype "passive+no_connect"))
    )
    (net (code "87") (name "unconnected-(J203-3V3-Pad19)") (class "Default")
      (node (ref "J203") (pin "19") (pinfunction "3V3_19") (pintype "passive+no_connect"))
    )
    (net (code "88") (name "unconnected-(J203-A9_{slash}_P31-Pad30)") (class "Default")
      (node (ref "J203") (pin "30") (pinfunction "A9_/_P31_30") (pintype "passive+no_connect"))
    )
    (net (code "89") (name "unconnected-(J203-B9_{slash}_P33-Pad28)") (class "Default")
      (node (ref "J203") (pin "28") (pinfunction "B9_/_P33_28") (pintype "passive+no_connect"))
    )
    (net (code "90") (name "unconnected-(J203-P11_{slash}_T8-Pad10)") (class "Default")
      (node (ref "J203") (pin "10") (pinfunction "P11_/_T8_10") (pintype "passive+no_connect"))
    )
    (net (code "91") (name "unconnected-(J203-P13_{slash}_R8-Pad8)") (class "Default")
      (node (ref "J203") (pin "8") (pinfunction "P13_/_R8_8") (pintype "passive+no_connect"))
    )
    (net (code "92") (name "unconnected-(J203-R9_{slash}_P25-Pad33)") (class "Default")
      (node (ref "J203") (pin "33") (pinfunction "R9_/_P25_33") (pintype "passive+no_connect"))
    )
    (net (code "93") (name "unconnected-(J203-T9_{slash}_P23-Pad34)") (class "Default")
      (node (ref "J203") (pin "34") (pinfunction "T9_/_P23_34") (pintype "passive+no_connect"))
    )
  )
)
